# Main.net
KiCad netlist of a schematic drawn in Altium Designer
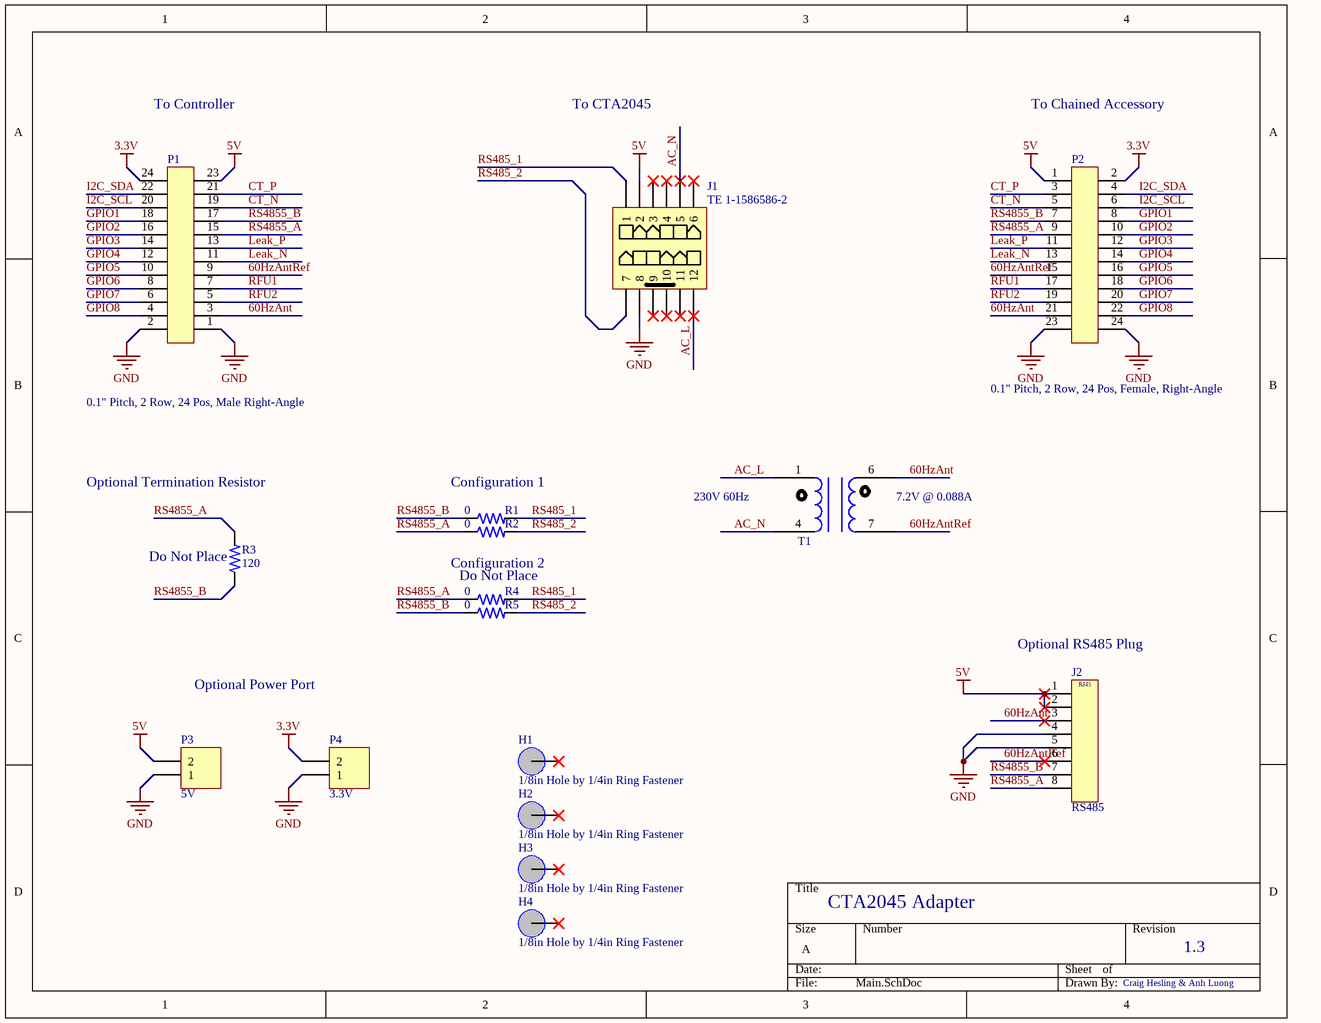
[diagram p0: Main.SchDoc]

(export (version "E")
  (design (tool "Eeschema 10.0.6"))
  (components
    (comp (ref "H1")
      (value "1/8in Hole by 1/4in Ring Fastener")
      (footprint "1/8in Fastener Hole")
      (libsource (lib "Misc") (part "1/8in by 1/4in Fastner Hole"))
    )
    (comp (ref "H2")
      (value "1/8in Hole by 1/4in Ring Fastener")
      (footprint "1/8in Fastener Hole")
      (libsource (lib "Misc") (part "1/8in by 1/4in Fastner Hole"))
    )
    (comp (ref "H3")
      (value "1/8in Hole by 1/4in Ring Fastener")
      (footprint "1/8in Fastener Hole")
      (libsource (lib "Misc") (part "1/8in by 1/4in Fastner Hole"))
    )
    (comp (ref "H4")
      (value "1/8in Hole by 1/4in Ring Fastener")
      (footprint "1/8in Fastener Hole")
      (libsource (lib "Misc") (part "1/8in by 1/4in Fastner Hole"))
    )
    (comp (ref "J1")
      (value "TE 1-1586586-2")
      (footprint "12POS 4.2mm Pitch Vertical")
      (description "TE Connectivity 1-1586586-2")
      (libsource (lib "Connectors") (part "12POS 4.2mm Pitch Vertical"))
    )
    (comp (ref "J2")
      (value "RS485")
      (footprint "RJ45 Unshielded PTH Connector")
      (description "Amphenol RJ45 Unshielded Through-Hole Connector")
      (fields
        (field (name "MANUFACTURER") "Amphenol FCI")
        (field (name "MANUFACTURER PART NUMBER") "54601-908WPLF")
      )
      (libsource (lib "Connectors") (part "RJ45 Unshielded PTH Connector"))
    )
    (comp (ref "P1")
      (value "0.1\" Pitch, 2 Row, 24 Pos, Male Right-Angle")
      (footprint "0.1 inch 2 row 24 pos male right-angle header Sullins")
      (description "Sullins 0.1\" 2 row 24 position male right-angle header")
      (libsource (lib "Connectors") (part "0.1{dblquote} 2 row 24 position male right-angle header sullins"))
    )
    (comp (ref "P2")
      (value "0.1\" Pitch, 2 Row, 24 Pos, Female, Right-Angle")
      (footprint "0.1 inch 2 row 24 pos female right-angle header Sullins")
      (description "Sullins 0.1\" 2 row 24 position female right-angle header")
      (libsource (lib "Connectors") (part "0.1{dblquote} 2 row 24 position female right-angle header sullins"))
    )
    (comp (ref "P3")
      (value "5V")
      (footprint "HDR1X2")
      (description "Header, 2-Pin")
      (fields (field (name "PUBLISHER") "Altium Limited"))
      (libsource (lib "Miscellaneous Connectors") (part "Header 2"))
    )
    (comp (ref "P4")
      (value "3.3V")
      (footprint "HDR1X2")
      (description "Header, 2-Pin")
      (fields (field (name "PUBLISHER") "Altium Limited"))
      (libsource (lib "Miscellaneous Connectors") (part "Header 2"))
    )
    (comp (ref "R1")
      (value "0")
      (footprint "RESC1608X06L - RES0603")
      (description "SMT 0603 Ceramic Resistor")
      (fields (field (name "POWER") "1/10W") (field (name "TOLERANCE") "Jumper"))
      (libsource (lib "Passives") (part "RES0603 0 Jumper 1/10W"))
    )
    (comp (ref "R2")
      (value "0")
      (footprint "RESC1608X06L - RES0603")
      (description "SMT 0603 Ceramic Resistor")
      (fields (field (name "POWER") "1/10W") (field (name "TOLERANCE") "Jumper"))
      (libsource (lib "Passives") (part "RES0603 0 Jumper 1/10W"))
    )
    (comp (ref "R3")
      (value "120")
      (footprint "RESC1608X06L - RES0603")
      (description "SMT 0603 Ceramic Resistor")
      (libsource (lib "Passives") (part "RES0603 120 1% 1/10W"))
    )
    (comp (ref "R4")
      (value "0")
      (footprint "RESC1608X06L - RES0603")
      (description "SMT 0603 Ceramic Resistor")
      (fields (field (name "POWER") "1/10W") (field (name "TOLERANCE") "Jumper"))
      (libsource (lib "Passives") (part "RES0603 0 Jumper 1/10W"))
    )
    (comp (ref "R5")
      (value "0")
      (footprint "RESC1608X06L - RES0603")
      (description "SMT 0603 Ceramic Resistor")
      (fields (field (name "POWER") "1/10W") (field (name "TOLERANCE") "Jumper"))
      (libsource (lib "Passives") (part "RES0603 0 Jumper 1/10W"))
    )
    (comp (ref "T1")
      (value "SPK00304")
      (footprint "SPK003")
      (description "Standard PCB-Transformers ¦ SPK-003 ¦ POWER 0.35 VA")
      (libsource (lib "Power") (part "SPK00304"))
    )
  )
  (nets
    (net (code "1") (name "/60HzAnt") (class "Default")
      (node (ref "J2") (pin "3") (pintype "passive"))
      (node (ref "P1") (pin "3") (pintype "passive"))
      (node (ref "P2") (pin "21") (pintype "passive"))
      (node (ref "T1") (pin "6") (pinfunction "6_6") (pintype "passive"))
    )
    (net (code "2") (name "/60HzAntRef") (class "Default")
      (node (ref "J2") (pin "6") (pintype "passive"))
      (node (ref "P1") (pin "9") (pintype "passive"))
      (node (ref "P2") (pin "15") (pintype "passive"))
      (node (ref "T1") (pin "7") (pinfunction "7_7") (pintype "passive"))
    )
    (net (code "3") (name "/AC_L") (class "Default")
      (node (ref "J1") (pin "12") (pinfunction "12_12") (pintype "passive"))
      (node (ref "T1") (pin "1") (pinfunction "1_1") (pintype "passive"))
    )
    (net (code "4") (name "/AC_N") (class "Default")
      (node (ref "J1") (pin "5") (pinfunction "5_5") (pintype "passive"))
      (node (ref "T1") (pin "4") (pinfunction "4_4") (pintype "passive"))
    )
    (net (code "5") (name "/CT_N") (class "Default")
      (node (ref "P1") (pin "19") (pintype "passive"))
      (node (ref "P2") (pin "5") (pintype "passive"))
    )
    (net (code "6") (name "/CT_P") (class "Default")
      (node (ref "P1") (pin "21") (pintype "passive"))
      (node (ref "P2") (pin "3") (pintype "passive"))
    )
    (net (code "7") (name "/GPIO1") (class "Default")
      (node (ref "P1") (pin "18") (pintype "passive"))
      (node (ref "P2") (pin "8") (pintype "passive"))
    )
    (net (code "8") (name "/GPIO2") (class "Default")
      (node (ref "P1") (pin "16") (pintype "passive"))
      (node (ref "P2") (pin "10") (pintype "passive"))
    )
    (net (code "9") (name "/GPIO3") (class "Default")
      (node (ref "P1") (pin "14") (pintype "passive"))
      (node (ref "P2") (pin "12") (pintype "passive"))
    )
    (net (code "10") (name "/GPIO4") (class "Default")
      (node (ref "P1") (pin "12") (pintype "passive"))
      (node (ref "P2") (pin "14") (pintype "passive"))
    )
    (net (code "11") (name "/GPIO5") (class "Default")
      (node (ref "P1") (pin "10") (pintype "passive"))
      (node (ref "P2") (pin "16") (pintype "passive"))
    )
    (net (code "12") (name "/GPIO6") (class "Default")
      (node (ref "P1") (pin "8") (pintype "passive"))
      (node (ref "P2") (pin "18") (pintype "passive"))
    )
    (net (code "13") (name "/GPIO7") (class "Default")
      (node (ref "P1") (pin "6") (pintype "passive"))
      (node (ref "P2") (pin "20") (pintype "passive"))
    )
    (net (code "14") (name "/GPIO8") (class "Default")
      (node (ref "P1") (pin "4") (pintype "passive"))
      (node (ref "P2") (pin "22") (pintype "passive"))
    )
    (net (code "15") (name "/I2C_SCL") (class "Default")
      (node (ref "P1") (pin "20") (pintype "passive"))
      (node (ref "P2") (pin "6") (pintype "passive"))
    )
    (net (code "16") (name "/I2C_SDA") (class "Default")
      (node (ref "P1") (pin "22") (pintype "passive"))
      (node (ref "P2") (pin "4") (pintype "passive"))
    )
    (net (code "17") (name "/Leak_N") (class "Default")
      (node (ref "P1") (pin "11") (pintype "passive"))
      (node (ref "P2") (pin "13") (pintype "passive"))
    )
    (net (code "18") (name "/Leak_P") (class "Default")
      (node (ref "P1") (pin "13") (pintype "passive"))
      (node (ref "P2") (pin "11") (pintype "passive"))
    )
    (net (code "19") (name "/RFU1") (class "Default")
      (node (ref "P1") (pin "7") (pintype "passive"))
      (node (ref "P2") (pin "17") (pintype "passive"))
    )
    (net (code "20") (name "/RFU2") (class "Default")
      (node (ref "P1") (pin "5") (pintype "passive"))
      (node (ref "P2") (pin "19") (pintype "passive"))
    )
    (net (code "21") (name "/RS485_1") (class "Default")
      (node (ref "J1") (pin "1") (pinfunction "1_1") (pintype "passive"))
      (node (ref "R1") (pin "2") (pinfunction "2_2") (pintype "passive"))
      (node (ref "R4") (pin "2") (pinfunction "2_2") (pintype "passive"))
    )
    (net (code "22") (name "/RS485_2") (class "Default")
      (node (ref "J1") (pin "7") (pinfunction "7_7") (pintype "passive"))
      (node (ref "R2") (pin "2") (pinfunction "2_2") (pintype "passive"))
      (node (ref "R5") (pin "2") (pinfunction "2_2") (pintype "passive"))
    )
    (net (code "23") (name "/RS4855_A") (class "Default")
      (node (ref "J2") (pin "8") (pintype "passive"))
      (node (ref "P1") (pin "15") (pintype "passive"))
      (node (ref "P2") (pin "9") (pintype "passive"))
      (node (ref "R2") (pin "1") (pinfunction "1_1") (pintype "passive"))
      (node (ref "R3") (pin "2") (pinfunction "2_2") (pintype "passive"))
      (node (ref "R4") (pin "1") (pinfunction "1_1") (pintype "passive"))
    )
    (net (code "24") (name "/RS4855_B") (class "Default")
      (node (ref "J2") (pin "7") (pintype "passive"))
      (node (ref "P1") (pin "17") (pintype "passive"))
      (node (ref "P2") (pin "7") (pintype "passive"))
      (node (ref "R1") (pin "1") (pinfunction "1_1") (pintype "passive"))
      (node (ref "R3") (pin "1") (pinfunction "1_1") (pintype "passive"))
      (node (ref "R5") (pin "1") (pinfunction "1_1") (pintype "passive"))
    )
    (net (code "25") (name "3.3V") (class "Default")
      (node (ref "P1") (pin "24") (pintype "passive"))
      (node (ref "P2") (pin "2") (pintype "passive"))
      (node (ref "P4") (pin "2") (pinfunction "2_2") (pintype "passive"))
    )
    (net (code "26") (name "5V") (class "Default")
      (node (ref "J1") (pin "2") (pinfunction "2_2") (pintype "passive"))
      (node (ref "J2") (pin "1") (pintype "passive"))
      (node (ref "J2") (pin "2") (pintype "passive"))
      (node (ref "P1") (pin "23") (pintype "passive"))
      (node (ref "P2") (pin "1") (pintype "passive"))
      (node (ref "P3") (pin "2") (pinfunction "2_2") (pintype "passive"))
    )
    (net (code "27") (name "GND") (class "Default")
      (node (ref "J1") (pin "8") (pinfunction "8_8") (pintype "passive"))
      (node (ref "J2") (pin "4") (pintype "passive"))
      (node (ref "J2") (pin "5") (pintype "passive"))
      (node (ref "P1") (pin "1") (pintype "passive"))
      (node (ref "P1") (pin "2") (pintype "passive"))
      (node (ref "P2") (pin "23") (pintype "passive"))
      (node (ref "P2") (pin "24") (pintype "passive"))
      (node (ref "P3") (pin "1") (pinfunction "1_1") (pintype "passive"))
      (node (ref "P4") (pin "1") (pinfunction "1_1") (pintype "passive"))
    )
    (net (code "28") (name "unconnected-(H1-Pad1)") (class "Default")
      (node (ref "H1") (pin "1") (pinfunction "1_1") (pintype "power_in+no_connect"))
    )
    (net (code "29") (name "unconnected-(H2-Pad1)") (class "Default")
      (node (ref "H2") (pin "1") (pinfunction "1_1") (pintype "power_in+no_connect"))
    )
    (net (code "30") (name "unconnected-(H3-Pad1)") (class "Default")
      (node (ref "H3") (pin "1") (pinfunction "1_1") (pintype "power_in+no_connect"))
    )
    (net (code "31") (name "unconnected-(H4-Pad1)") (class "Default")
      (node (ref "H4") (pin "1") (pinfunction "1_1") (pintype "power_in+no_connect"))
    )
    (net (code "32") (name "unconnected-(J1-Pad3)") (class "Default")
      (node (ref "J1") (pin "3") (pinfunction "3_3") (pintype "passive+no_connect"))
    )
    (net (code "33") (name "unconnected-(J1-Pad4)") (class "Default")
      (node (ref "J1") (pin "4") (pinfunction "4_4") (pintype "passive+no_connect"))
    )
    (net (code "34") (name "unconnected-(J1-Pad6)") (class "Default")
      (node (ref "J1") (pin "6") (pinfunction "6_6") (pintype "passive+no_connect"))
    )
    (net (code "35") (name "unconnected-(J1-Pad9)") (class "Default")
      (node (ref "J1") (pin "9") (pinfunction "9_9") (pintype "passive+no_connect"))
    )
    (net (code "36") (name "unconnected-(J1-Pad10)") (class "Default")
      (node (ref "J1") (pin "10") (pinfunction "10_10") (pintype "passive+no_connect"))
    )
    (net (code "37") (name "unconnected-(J1-Pad11)") (class "Default")
      (node (ref "J1") (pin "11") (pinfunction "11_11") (pintype "passive+no_connect"))
    )
  )
)
